# rx_sensor.net
KiCad netlist of a schematic drawn in EAGLE
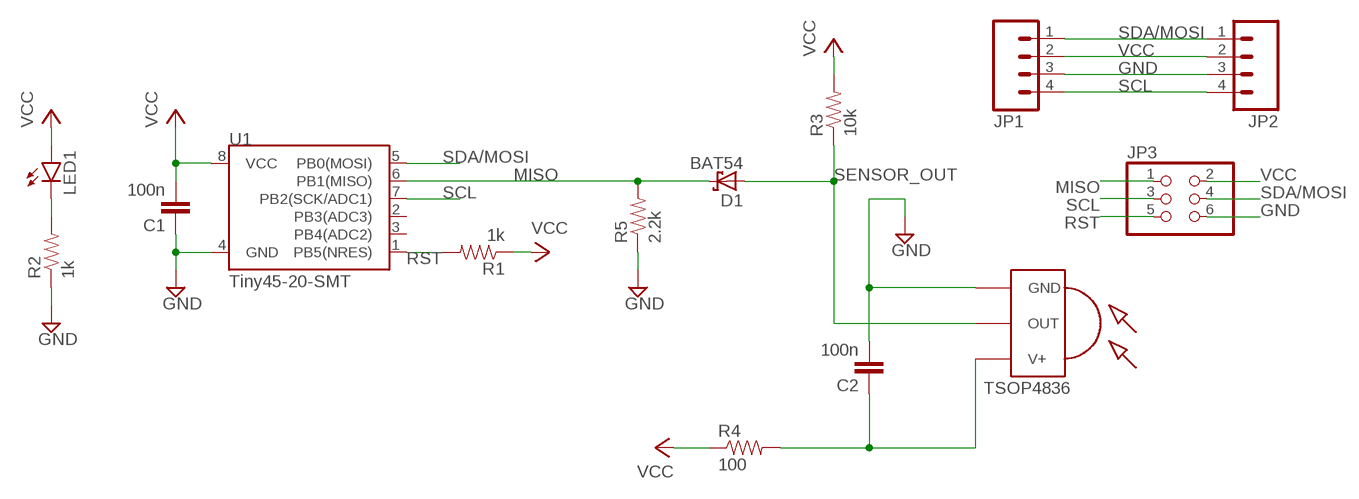
[diagram p0: schematic, sheet 1]

(export (version "E")
  (design (tool "Eeschema 10.0.6"))
  (components
    (comp (ref "C1")
      (value "100n")
      (footprint "eagle-import:0603-CAP")
      (libsource (lib "eagle-import") (part "CAP0603-CAP"))
    )
    (comp (ref "C2")
      (value "100n")
      (footprint "eagle-import:0603-CAP")
      (libsource (lib "eagle-import") (part "CAP0603-CAP"))
    )
    (comp (ref "D1")
      (value "BAT54")
      (footprint "eagle-import:SOT23")
      (libsource (lib "eagle-import") (part "BAT54"))
    )
    (comp (ref "JP1")
      (value "M04JST-PTH")
      (footprint "eagle-import:JST-4-PTH")
      (libsource (lib "eagle-import") (part "M04JST-PTH"))
    )
    (comp (ref "JP2")
      (value "M04JST-PTH")
      (footprint "eagle-import:JST-4-PTH")
      (libsource (lib "eagle-import") (part "M04JST-PTH"))
    )
    (comp (ref "JP3")
      (value "PINHD-2X3")
      (footprint "eagle-import:2X03")
      (libsource (lib "eagle-import") (part "PINHD-2X3"))
    )
    (comp (ref "LED1")
      (value "LED0603")
      (footprint "eagle-import:LED-0603")
      (libsource (lib "eagle-import") (part "LED0603"))
    )
    (comp (ref "R1")
      (value "1k")
      (footprint "eagle-import:0603-RES")
      (libsource (lib "eagle-import") (part "RESISTOR0603"))
    )
    (comp (ref "R2")
      (value "1k")
      (footprint "eagle-import:0603-RES")
      (libsource (lib "eagle-import") (part "RESISTOR0603"))
    )
    (comp (ref "R3")
      (value "10k")
      (footprint "eagle-import:0603-RES")
      (libsource (lib "eagle-import") (part "RESISTOR0603"))
    )
    (comp (ref "R4")
      (value "100")
      (footprint "eagle-import:0603-RES")
      (libsource (lib "eagle-import") (part "RESISTOR0603"))
    )
    (comp (ref "R5")
      (value "2.2k")
      (footprint "eagle-import:0603-RES")
      (libsource (lib "eagle-import") (part "RESISTOR0603"))
    )
    (comp (ref "TSOP4836")
      (value "TSOP4836")
      (footprint "eagle-import:TSOP18XX")
      (libsource (lib "eagle-import") (part "TSOP4836"))
    )
    (comp (ref "U1")
      (value "Tiny45-20-SMT")
      (footprint "eagle-import:SO08-EIAJ")
      (libsource (lib "eagle-import") (part "ATTINY45TINY45-20-SMT"))
    )
  )
  (nets
    (net (code "1") (name "/MISO") (class "Default")
      (node (ref "D1") (pin "3") (pinfunction "C_3") (pintype "passive"))
      (node (ref "JP3") (pin "1") (pinfunction "1_1") (pintype "passive"))
      (node (ref "R5") (pin "2") (pinfunction "2_2") (pintype "passive"))
      (node (ref "U1") (pin "6") (pinfunction "PB1(MISO)_6") (pintype "bidirectional"))
    )
    (net (code "2") (name "/RST") (class "Default")
      (node (ref "JP3") (pin "5") (pinfunction "5_5") (pintype "passive"))
      (node (ref "R1") (pin "2") (pinfunction "2_2") (pintype "passive"))
      (node (ref "U1") (pin "1") (pinfunction "PB5(NRES)_1") (pintype "bidirectional"))
    )
    (net (code "3") (name "/SCL") (class "Default")
      (node (ref "JP1") (pin "4") (pinfunction "4_4") (pintype "passive"))
      (node (ref "JP2") (pin "4") (pinfunction "4_4") (pintype "passive"))
      (node (ref "JP3") (pin "3") (pinfunction "3_3") (pintype "passive"))
      (node (ref "U1") (pin "7") (pinfunction "PB2(SCK/ADC1)_7") (pintype "bidirectional"))
    )
    (net (code "4") (name "/SDA{slash}MOSI") (class "Default")
      (node (ref "JP1") (pin "1") (pinfunction "1_1") (pintype "passive"))
      (node (ref "JP2") (pin "1") (pinfunction "1_1") (pintype "passive"))
      (node (ref "JP3") (pin "4") (pinfunction "4_4") (pintype "passive"))
      (node (ref "U1") (pin "5") (pinfunction "PB0(MOSI)_5") (pintype "bidirectional"))
    )
    (net (code "5") (name "/SENSOR_OUT") (class "Default")
      (node (ref "D1") (pin "1") (pinfunction "A_1") (pintype "passive"))
      (node (ref "R3") (pin "1") (pinfunction "1_1") (pintype "passive"))
      (node (ref "TSOP4836") (pin "OUT") (pinfunction "OUT_OUT") (pintype "bidirectional"))
    )
    (net (code "6") (name "GND") (class "Default")
      (node (ref "C1") (pin "1") (pinfunction "1_1") (pintype "passive"))
      (node (ref "C2") (pin "2") (pinfunction "2_2") (pintype "passive"))
      (node (ref "JP1") (pin "3") (pinfunction "3_3") (pintype "passive"))
      (node (ref "JP2") (pin "3") (pinfunction "3_3") (pintype "passive"))
      (node (ref "JP3") (pin "6") (pinfunction "6_6") (pintype "passive"))
      (node (ref "R2") (pin "1") (pinfunction "1_1") (pintype "passive"))
      (node (ref "R5") (pin "1") (pinfunction "1_1") (pintype "passive"))
      (node (ref "TSOP4836") (pin "GND") (pinfunction "GND_GND") (pintype "bidirectional"))
      (node (ref "U1") (pin "4") (pinfunction "GND_4") (pintype "bidirectional"))
    )
    (net (code "7") (name "Net-(LED1-PadC)") (class "Default")
      (node (ref "LED1") (pin "C") (pinfunction "C_C") (pintype "passive"))
      (node (ref "R2") (pin "2") (pinfunction "2_2") (pintype "passive"))
    )
    (net (code "8") (name "Net-(TSOP4836-V+)") (class "Default")
      (node (ref "C2") (pin "1") (pinfunction "1_1") (pintype "passive"))
      (node (ref "R4") (pin "2") (pinfunction "2_2") (pintype "passive"))
      (node (ref "TSOP4836") (pin "VCC") (pinfunction "V+_VCC") (pintype "bidirectional"))
    )
    (net (code "9") (name "VCC") (class "Default")
      (node (ref "C1") (pin "2") (pinfunction "2_2") (pintype "passive"))
      (node (ref "JP1") (pin "2") (pinfunction "2_2") (pintype "passive"))
      (node (ref "JP2") (pin "2") (pinfunction "2_2") (pintype "passive"))
      (node (ref "JP3") (pin "2") (pinfunction "2_2") (pintype "passive"))
      (node (ref "LED1") (pin "A") (pinfunction "A_A") (pintype "passive"))
      (node (ref "R1") (pin "1") (pinfunction "1_1") (pintype "passive"))
      (node (ref "R3") (pin "2") (pinfunction "2_2") (pintype "passive"))
      (node (ref "R4") (pin "1") (pinfunction "1_1") (pintype "passive"))
      (node (ref "U1") (pin "8") (pinfunction "VCC_8") (pintype "bidirectional"))
    )
    (net (code "10") (name "unconnected-(U1-PB3(ADC3)-Pad2)") (class "Default")
      (node (ref "U1") (pin "2") (pinfunction "PB3(ADC3)_2") (pintype "bidirectional"))
    )
    (net (code "11") (name "unconnected-(U1-PB4(ADC2)-Pad3)") (class "Default")
      (node (ref "U1") (pin "3") (pinfunction "PB4(ADC2)_3") (pintype "bidirectional"))
    )
  )
)
